# motion_sensor.net
KiCad netlist of a schematic drawn in EAGLE
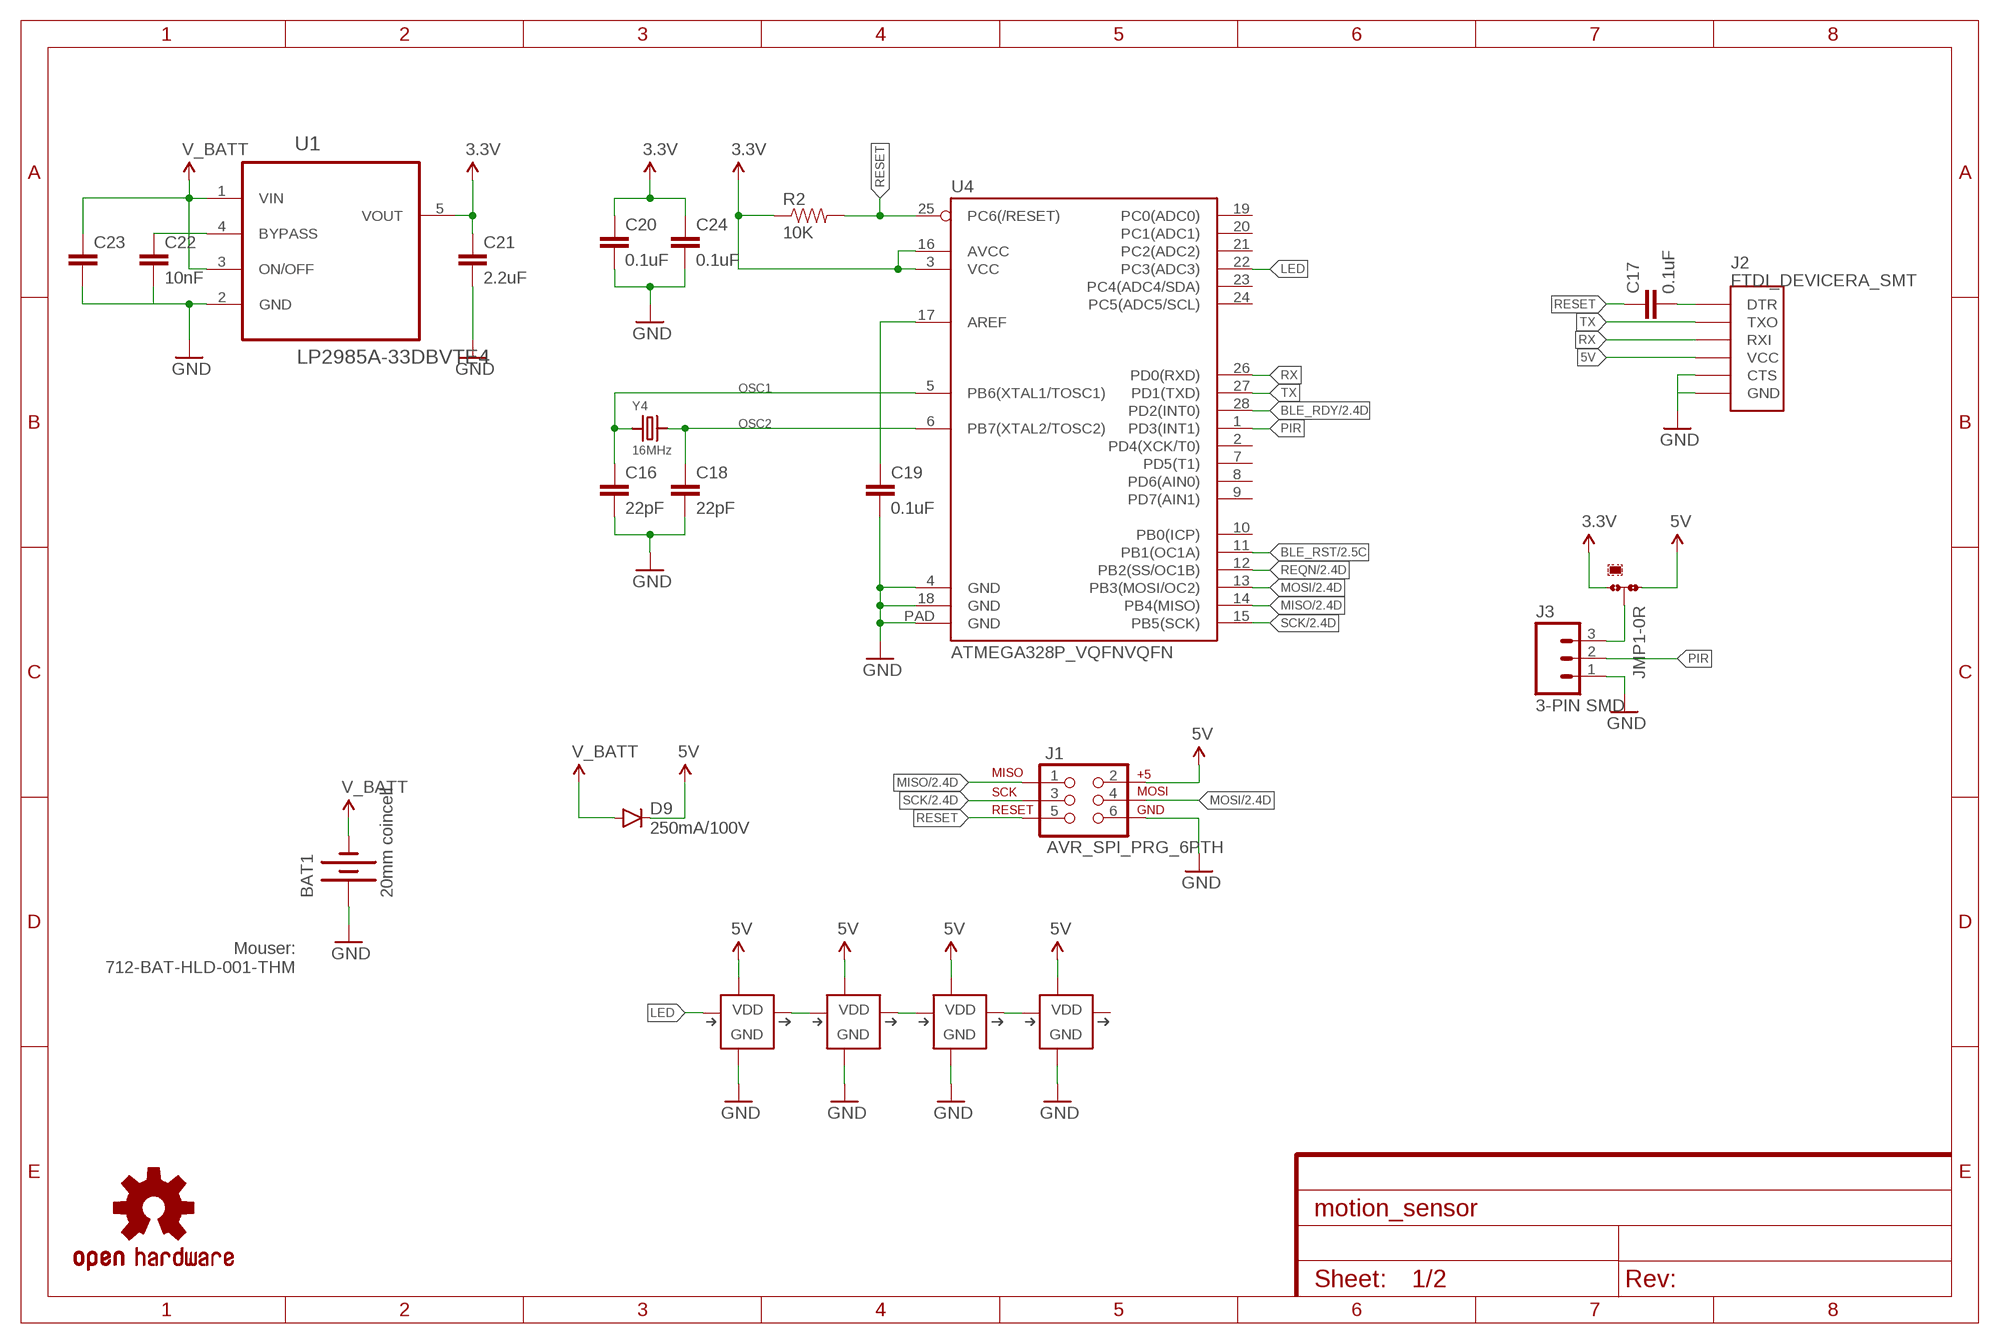
[diagram p0: schematic, sheet 1]
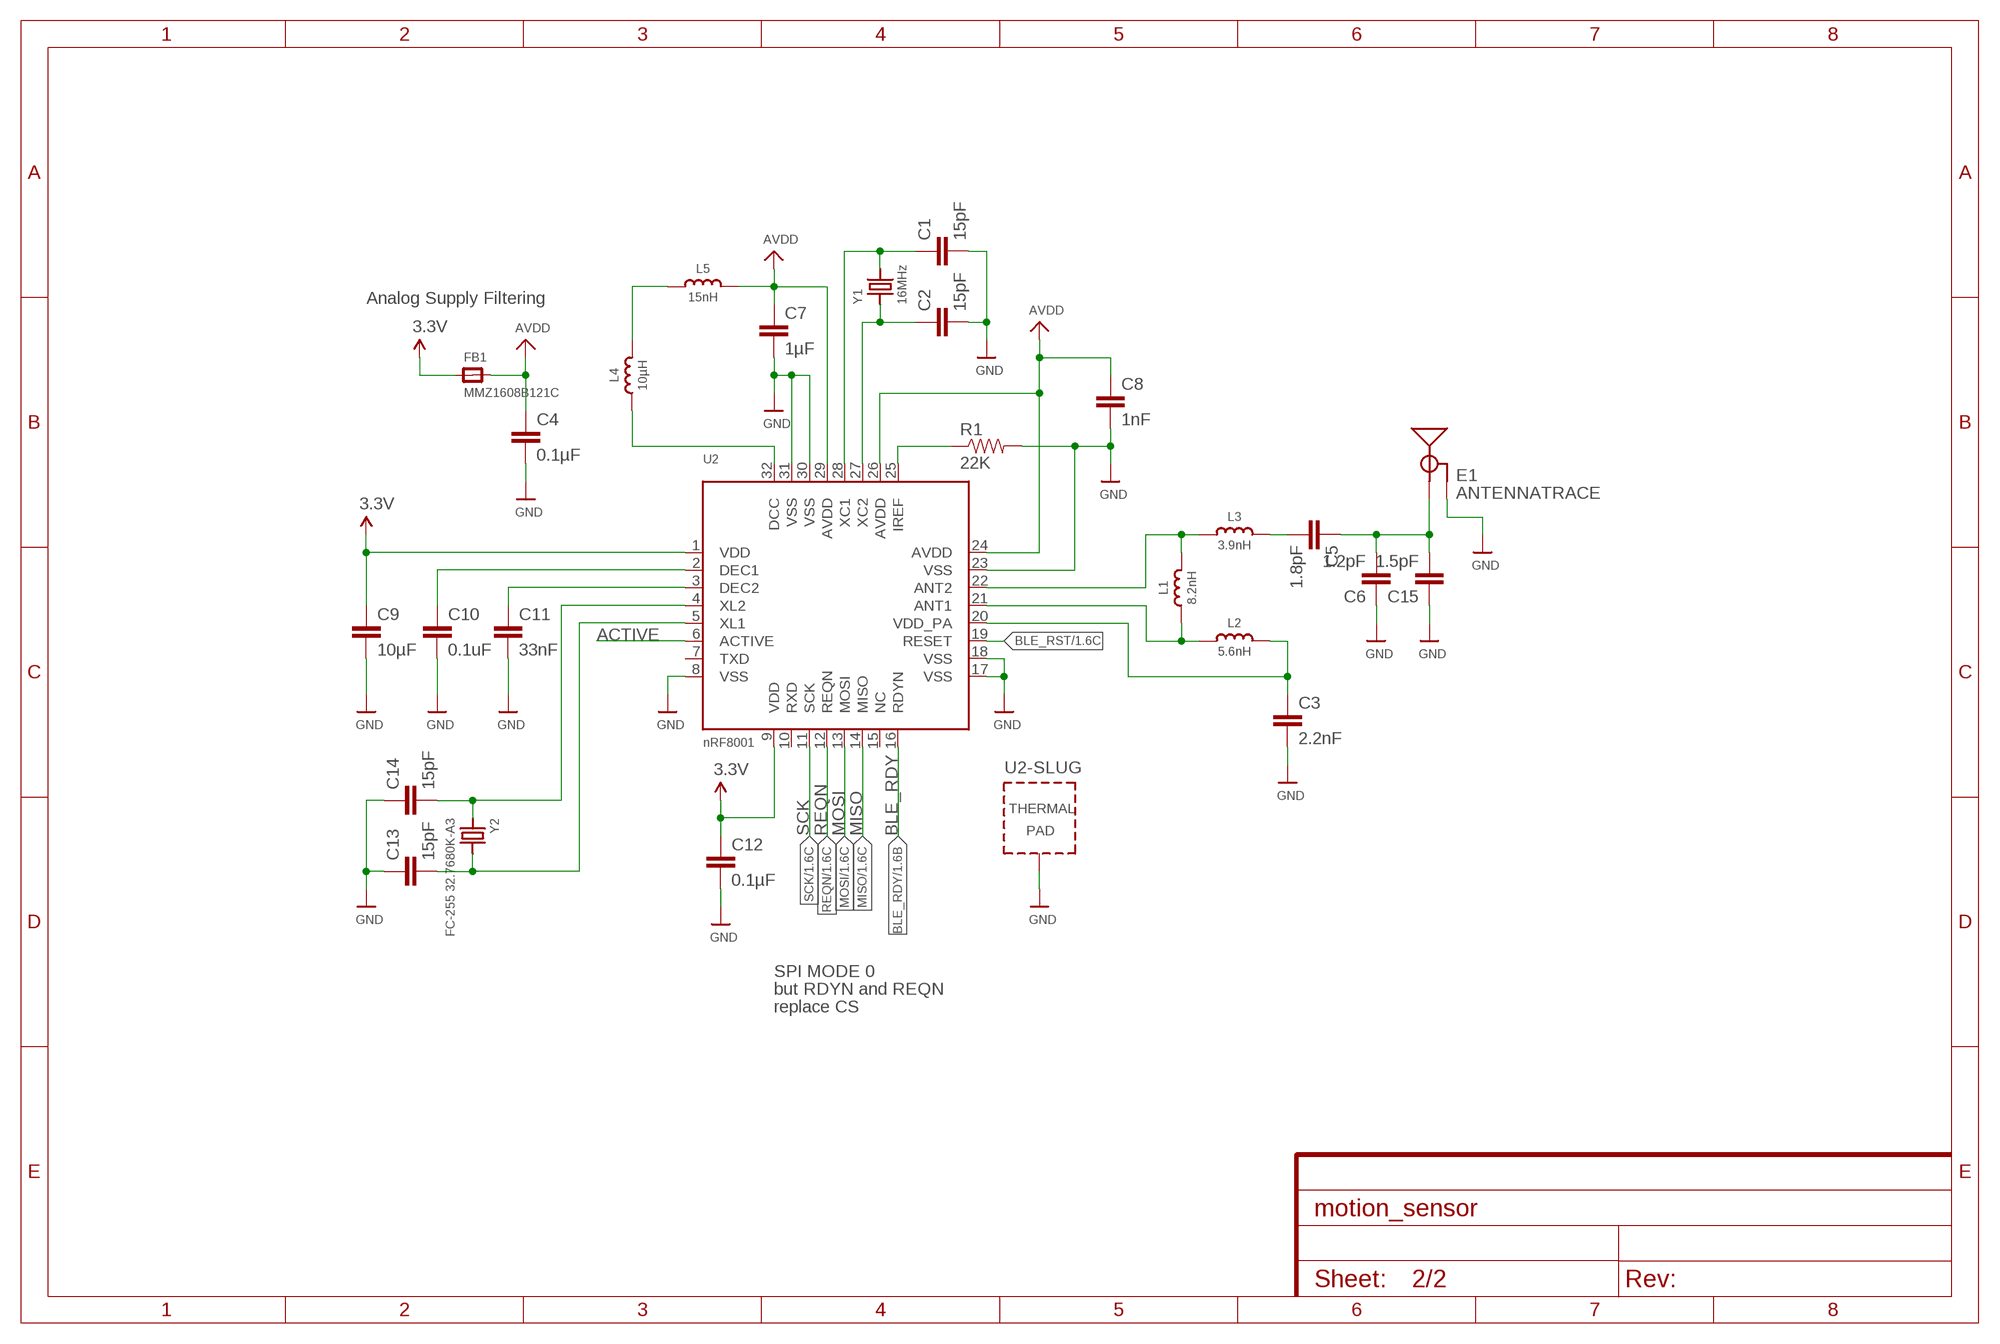
[diagram p1: schematic, sheet 2]

(export (version "E")
  (design (tool "Eeschema 10.0.6"))
  (components
    (comp (ref "BAT1")
      (value "20mm coincell")
      (footprint "eagle-import:BATTCON_20MM_4LEGS")
      (libsource (lib "eagle-import") (part "BATTERY20MM_4LEGS"))
    )
    (comp (ref "C16")
      (value "22pF")
      (footprint "eagle-import:0603-CAP")
      (libsource (lib "eagle-import") (part "22PF-50V-5%(0603)"))
    )
    (comp (ref "C17")
      (value "0.1uF")
      (footprint "eagle-import:0603-CAP")
      (libsource (lib "eagle-import") (part "0.1UF-25V(+80/-20%)(0603)"))
    )
    (comp (ref "C18")
      (value "22pF")
      (footprint "eagle-import:0603-CAP")
      (libsource (lib "eagle-import") (part "22PF-50V-5%(0603)"))
    )
    (comp (ref "C19")
      (value "0.1uF")
      (footprint "eagle-import:0603-CAP")
      (libsource (lib "eagle-import") (part "0.1UF-25V(+80/-20%)(0603)"))
    )
    (comp (ref "C20")
      (value "0.1uF")
      (footprint "eagle-import:0603-CAP")
      (libsource (lib "eagle-import") (part "0.1UF-25V(+80/-20%)(0603)"))
    )
    (comp (ref "C21")
      (value "2.2uF")
      (footprint "eagle-import:0603-CAP")
      (libsource (lib "eagle-import") (part "2.2UF-10V-20%(0603)"))
    )
    (comp (ref "C22")
      (value "10nF")
      (footprint "eagle-import:0603-CAP")
      (libsource (lib "eagle-import") (part "10NF/10000PF-50V-10%(0603)"))
    )
    (comp (ref "C23")
      (value "1UF-25V-10%(0805)\"")
      (footprint "eagle-import:0805-CAP")
      (libsource (lib "eagle-import") (part "1UF-25V-10%(0805){dblquote}"))
    )
    (comp (ref "C24")
      (value "0.1uF")
      (footprint "eagle-import:0603-CAP")
      (libsource (lib "eagle-import") (part "0.1UF-25V(+80/-20%)(0603)"))
    )
    (comp (ref "D9")
      (value "250mA/100V")
      (footprint "eagle-import:SOD-323")
      (libsource (lib "eagle-import") (part "DIODEBAS16"))
    )
    (comp (ref "J1")
      (value "AVR_SPI_PRG_6PTH")
      (footprint "eagle-import:2X3")
      (libsource (lib "eagle-import") (part "AVR_SPI_PRG_6PTH"))
    )
    (comp (ref "J2")
      (value "FTDI_DEVICERA_SMT")
      (footprint "eagle-import:FTDI_DEVICE_RA_SMT")
      (libsource (lib "eagle-import") (part "FTDI_DEVICERA_SMT"))
    )
    (comp (ref "J3")
      (value "3-PIN SMD")
      (footprint "eagle-import:JST-3-SMD")
      (libsource (lib "eagle-import") (part "M03JST-SMD"))
    )
    (comp (ref "JMP1")
      (value "0R-JUMPC")
      (footprint "eagle-import:C0R-JMP")
      (libsource (lib "eagle-import") (part "0R-JUMPC"))
    )
    (comp (ref "LOGO1")
      (value "OSHW-LOGOS")
      (footprint "eagle-import:OSHW-LOGO-S")
      (libsource (lib "eagle-import") (part "OSHW-LOGOS"))
    )
    (comp (ref "R2")
      (value "10K")
      (footprint "eagle-import:0603-RES")
      (libsource (lib "eagle-import") (part "RESISTOR0603-RES"))
    )
    (comp (ref "U$1")
      (value "SK6812MINI")
      (footprint "eagle-import:LED-3535")
      (libsource (lib "eagle-import") (part "SK6812MINI"))
    )
    (comp (ref "U$11")
      (value "SK6812MINI")
      (footprint "eagle-import:LED-3535")
      (libsource (lib "eagle-import") (part "SK6812MINI"))
    )
    (comp (ref "U$15")
      (value "SK6812MINI")
      (footprint "eagle-import:LED-3535")
      (libsource (lib "eagle-import") (part "SK6812MINI"))
    )
    (comp (ref "U$17")
      (value "SK6812MINI")
      (footprint "eagle-import:LED-3535")
      (libsource (lib "eagle-import") (part "SK6812MINI"))
    )
    (comp (ref "U1")
      (value "LP2985A-33DBVTE4")
      (footprint "eagle-import:SOT95P280X145-5N")
      (libsource (lib "eagle-import") (part "LP2985A-33DBVTE4"))
    )
    (comp (ref "U4")
      (value "ATMEGA328P_VQFNVQFN")
      (footprint "eagle-import:VQFN-28")
      (libsource (lib "eagle-import") (part "ATMEGA328P_VQFNVQFN"))
    )
    (comp (ref "Y4")
      (value "16MHz")
      (footprint "eagle-import:CRYSTAL_3.2X2.5")
      (libsource (lib "eagle-import") (part "CRYSTAL3.2X2.5"))
    )
    (comp (ref "C1")
      (value "15pF")
      (footprint "eagle-import:0805")
      (libsource (lib "eagle-import") (part "CAP0805"))
    )
    (comp (ref "C2")
      (value "15pF")
      (footprint "eagle-import:0805")
      (libsource (lib "eagle-import") (part "CAP0805"))
    )
    (comp (ref "C3")
      (value "2.2nF")
      (footprint "eagle-import:0805")
      (libsource (lib "eagle-import") (part "CAP0805"))
    )
    (comp (ref "C4")
      (value "0.1µF")
      (footprint "eagle-import:0805")
      (libsource (lib "eagle-import") (part "CAP0805"))
    )
    (comp (ref "C5")
      (value "1.8pF")
      (footprint "eagle-import:0805")
      (libsource (lib "eagle-import") (part "CAP0805"))
    )
    (comp (ref "C6")
      (value "1.2pF")
      (footprint "eagle-import:0805")
      (libsource (lib "eagle-import") (part "CAP0805"))
    )
    (comp (ref "C7")
      (value "1µF")
      (footprint "eagle-import:0805")
      (libsource (lib "eagle-import") (part "CAP0805"))
    )
    (comp (ref "C8")
      (value "1nF")
      (footprint "eagle-import:0805")
      (libsource (lib "eagle-import") (part "CAP0805"))
    )
    (comp (ref "C9")
      (value "10µF")
      (footprint "eagle-import:0805")
      (libsource (lib "eagle-import") (part "CAP0805"))
    )
    (comp (ref "C10")
      (value "0.1uF")
      (footprint "eagle-import:0805")
      (libsource (lib "eagle-import") (part "CAP0805"))
    )
    (comp (ref "C11")
      (value "33nF")
      (footprint "eagle-import:0805")
      (libsource (lib "eagle-import") (part "CAP0805"))
    )
    (comp (ref "C12")
      (value "0.1µF")
      (footprint "eagle-import:0805")
      (libsource (lib "eagle-import") (part "CAP0805"))
    )
    (comp (ref "C13")
      (value "15pF")
      (footprint "eagle-import:0805")
      (libsource (lib "eagle-import") (part "CAP0805"))
    )
    (comp (ref "C14")
      (value "15pF")
      (footprint "eagle-import:0805")
      (libsource (lib "eagle-import") (part "CAP0805"))
    )
    (comp (ref "C15")
      (value "1.5pF")
      (footprint "eagle-import:0805")
      (libsource (lib "eagle-import") (part "CAP0805"))
    )
    (comp (ref "E1")
      (value "ANTENNATRACE")
      (footprint "eagle-import:TRACE_ANTENNA_2.4GHZ_25.7MM")
      (libsource (lib "eagle-import") (part "ANTENNATRACE"))
    )
    (comp (ref "FB1")
      (value "MMZ1608B121C")
      (footprint "eagle-import:0805")
      (libsource (lib "eagle-import") (part "FERRITE0805"))
    )
    (comp (ref "L1")
      (value "8.2nH")
      (footprint "eagle-import:_0402")
      (libsource (lib "eagle-import") (part "INDUCTOR_0402"))
    )
    (comp (ref "L2")
      (value "5.6nH")
      (footprint "eagle-import:_0402")
      (libsource (lib "eagle-import") (part "INDUCTOR_0402"))
    )
    (comp (ref "L3")
      (value "3.9nH")
      (footprint "eagle-import:_0402")
      (libsource (lib "eagle-import") (part "INDUCTOR_0402"))
    )
    (comp (ref "L4")
      (value "10µH")
      (footprint "eagle-import:_0603")
      (libsource (lib "eagle-import") (part "INDUCTOR_0603"))
    )
    (comp (ref "L5")
      (value "15nH")
      (footprint "eagle-import:_0603")
      (libsource (lib "eagle-import") (part "INDUCTOR_0603"))
    )
    (comp (ref "R1")
      (value "22K")
      (footprint "eagle-import:0603-RES")
      (libsource (lib "eagle-import") (part "RESISTOR0603-RES"))
    )
    (comp (ref "U2")
      (value "nRF8001")
      (footprint "eagle-import:QFN32_5MM")
      (libsource (lib "eagle-import") (part "NRF8001"))
    )
    (comp (ref "Y1")
      (value "16MHz")
      (footprint "eagle-import:CRYSTAL_3.2X2.5")
      (libsource (lib "eagle-import") (part "CRYSTAL3.2X2.5"))
    )
    (comp (ref "Y2")
      (value "FC-255 32.7680K-A3")
      (footprint "eagle-import:CRYSTAL_8X3.8")
      (libsource (lib "eagle-import") (part "CRYSTAL8.0X3.8"))
    )
  )
  (nets
    (net (code "1") (name "3.3V") (class "Default")
      (node (ref "C12") (pin "1") (pinfunction "1_1") (pintype "passive"))
      (node (ref "C20") (pin "1") (pinfunction "1_1") (pintype "passive"))
      (node (ref "C21") (pin "1") (pinfunction "1_1") (pintype "passive"))
      (node (ref "C24") (pin "1") (pinfunction "1_1") (pintype "passive"))
      (node (ref "C9") (pin "1") (pinfunction "1_1") (pintype "passive"))
      (node (ref "FB1") (pin "1") (pinfunction "P$1_1") (pintype "passive"))
      (node (ref "JMP1") (pin "3") (pinfunction "3_3") (pintype "passive"))
      (node (ref "R2") (pin "1") (pinfunction "1_1") (pintype "passive"))
      (node (ref "U1") (pin "5") (pinfunction "VOUT_5") (pintype "output"))
      (node (ref "U2") (pin "1") (pinfunction "VDD_1") (pintype "power_in"))
      (node (ref "U2") (pin "9") (pinfunction "VDD_9") (pintype "power_in"))
      (node (ref "U4") (pin "16") (pinfunction "AVCC_16") (pintype "bidirectional"))
      (node (ref "U4") (pin "3") (pinfunction "VCC_3") (pintype "bidirectional"))
    )
    (net (code "2") (name "5V") (class "Default")
      (node (ref "D9") (pin "C") (pinfunction "C_C") (pintype "passive"))
      (node (ref "J1") (pin "2") (pinfunction "2_2") (pintype "passive"))
      (node (ref "J2") (pin "4") (pinfunction "VCC_4") (pintype "bidirectional"))
      (node (ref "JMP1") (pin "1") (pinfunction "1_1") (pintype "passive"))
      (node (ref "U$1") (pin "3") (pinfunction "VDD_3") (pintype "power_in"))
      (node (ref "U$11") (pin "3") (pinfunction "VDD_3") (pintype "power_in"))
      (node (ref "U$15") (pin "3") (pinfunction "VDD_3") (pintype "power_in"))
      (node (ref "U$17") (pin "3") (pinfunction "VDD_3") (pintype "power_in"))
    )
    (net (code "3") (name "ACTIVE") (class "Default")
      (node (ref "U2") (pin "6") (pinfunction "ACTIVE_6") (pintype "output"))
    )
    (net (code "4") (name "AVDD") (class "Default")
      (node (ref "C4") (pin "1") (pinfunction "1_1") (pintype "passive"))
      (node (ref "C7") (pin "1") (pinfunction "1_1") (pintype "passive"))
      (node (ref "C8") (pin "1") (pinfunction "1_1") (pintype "passive"))
      (node (ref "FB1") (pin "2") (pinfunction "P$2_2") (pintype "passive"))
      (node (ref "L5") (pin "2") (pinfunction "2_2") (pintype "passive"))
      (node (ref "U2") (pin "24") (pinfunction "AVDD_24") (pintype "power_in"))
      (node (ref "U2") (pin "26") (pinfunction "AVDD_26") (pintype "power_in"))
      (node (ref "U2") (pin "29") (pinfunction "AVDD_29") (pintype "power_in"))
    )
    (net (code "5") (name "BLE_RDY") (class "Default")
      (node (ref "U2") (pin "16") (pinfunction "RDYN_16") (pintype "output"))
      (node (ref "U4") (pin "28") (pinfunction "PD2(INT0)_28") (pintype "bidirectional"))
    )
    (net (code "6") (name "BLE_RST") (class "Default")
      (node (ref "U2") (pin "19") (pinfunction "RESET_19") (pintype "input"))
      (node (ref "U4") (pin "11") (pinfunction "PB1(OC1A)_11") (pintype "bidirectional"))
    )
    (net (code "7") (name "GND") (class "Default")
      (node (ref "BAT1") (pin "POSITIVE@1") (pinfunction "+_POSITIVE@1") (pintype "power_in"))
      (node (ref "BAT1") (pin "POSITIVE@2") (pinfunction "+_POSITIVE@2") (pintype "power_in"))
      (node (ref "BAT1") (pin "POSITIVE@3") (pinfunction "+_POSITIVE@3") (pintype "power_in"))
      (node (ref "BAT1") (pin "POSITIVE@4") (pinfunction "+_POSITIVE@4") (pintype "power_in"))
      (node (ref "C1") (pin "2") (pinfunction "2_2") (pintype "passive"))
      (node (ref "C10") (pin "2") (pinfunction "2_2") (pintype "passive"))
      (node (ref "C11") (pin "2") (pinfunction "2_2") (pintype "passive"))
      (node (ref "C12") (pin "2") (pinfunction "2_2") (pintype "passive"))
      (node (ref "C13") (pin "1") (pinfunction "1_1") (pintype "passive"))
      (node (ref "C14") (pin "1") (pinfunction "1_1") (pintype "passive"))
      (node (ref "C15") (pin "1") (pinfunction "1_1") (pintype "passive"))
      (node (ref "C16") (pin "2") (pinfunction "2_2") (pintype "passive"))
      (node (ref "C18") (pin "2") (pinfunction "2_2") (pintype "passive"))
      (node (ref "C19") (pin "2") (pinfunction "2_2") (pintype "passive"))
      (node (ref "C2") (pin "2") (pinfunction "2_2") (pintype "passive"))
      (node (ref "C20") (pin "2") (pinfunction "2_2") (pintype "passive"))
      (node (ref "C21") (pin "2") (pinfunction "2_2") (pintype "passive"))
      (node (ref "C22") (pin "2") (pinfunction "2_2") (pintype "passive"))
      (node (ref "C23") (pin "2") (pinfunction "2_2") (pintype "passive"))
      (node (ref "C24") (pin "2") (pinfunction "2_2") (pintype "passive"))
      (node (ref "C3") (pin "2") (pinfunction "2_2") (pintype "passive"))
      (node (ref "C4") (pin "2") (pinfunction "2_2") (pintype "passive"))
      (node (ref "C6") (pin "1") (pinfunction "1_1") (pintype "passive"))
      (node (ref "C7") (pin "2") (pinfunction "2_2") (pintype "passive"))
      (node (ref "C8") (pin "2") (pinfunction "2_2") (pintype "passive"))
      (node (ref "C9") (pin "2") (pinfunction "2_2") (pintype "passive"))
      (node (ref "E1") (pin "GND") (pinfunction "GND_GND") (pintype "bidirectional"))
      (node (ref "E1") (pin "GND2") (pinfunction "GND_GND2") (pintype "bidirectional"))
      (node (ref "J1") (pin "6") (pinfunction "6_6") (pintype "passive"))
      (node (ref "J2") (pin "5") (pinfunction "CTS_5") (pintype "bidirectional"))
      (node (ref "J2") (pin "6") (pinfunction "GND_6") (pintype "bidirectional"))
      (node (ref "J3") (pin "1") (pinfunction "1_1") (pintype "passive"))
      (node (ref "R1") (pin "2") (pinfunction "2_2") (pintype "passive"))
      (node (ref "U$1") (pin "1") (pinfunction "GND_1") (pintype "power_in"))
      (node (ref "U$11") (pin "1") (pinfunction "GND_1") (pintype "power_in"))
      (node (ref "U$15") (pin "1") (pinfunction "GND_1") (pintype "power_in"))
      (node (ref "U$17") (pin "1") (pinfunction "GND_1") (pintype "power_in"))
      (node (ref "U1") (pin "2") (pinfunction "GND_2") (pintype "passive"))
      (node (ref "U2") (pin "17") (pinfunction "VSS_17") (pintype "power_in"))
      (node (ref "U2") (pin "18") (pinfunction "VSS_18") (pintype "power_in"))
      (node (ref "U2") (pin "23") (pinfunction "VSS_23") (pintype "power_in"))
      (node (ref "U2") (pin "30") (pinfunction "VSS_30") (pintype "power_in"))
      (node (ref "U2") (pin "31") (pinfunction "VSS_31") (pintype "power_in"))
      (node (ref "U2") (pin "33") (pinfunction "TP_33") (pintype "power_in"))
      (node (ref "U2") (pin "8") (pinfunction "VSS_8") (pintype "power_in"))
      (node (ref "U4") (pin "18") (pinfunction "GND_18") (pintype "bidirectional"))
      (node (ref "U4") (pin "4") (pinfunction "GND_4") (pintype "bidirectional"))
      (node (ref "U4") (pin "PAD") (pinfunction "GND_PAD") (pintype "bidirectional"))
    )
    (net (code "8") (name "LED") (class "Default")
      (node (ref "U$1") (pin "2") (pinfunction "DI_2") (pintype "input"))
      (node (ref "U4") (pin "22") (pinfunction "PC3(ADC3)_22") (pintype "bidirectional"))
    )
    (net (code "9") (name "MISO") (class "Default")
      (node (ref "J1") (pin "1") (pinfunction "1_1") (pintype "passive"))
      (node (ref "U2") (pin "14") (pinfunction "MISO_14") (pintype "output"))
      (node (ref "U4") (pin "14") (pinfunction "PB4(MISO)_14") (pintype "bidirectional"))
    )
    (net (code "10") (name "MOSI") (class "Default")
      (node (ref "J1") (pin "4") (pinfunction "4_4") (pintype "passive"))
      (node (ref "U2") (pin "13") (pinfunction "MOSI_13") (pintype "input"))
      (node (ref "U4") (pin "13") (pinfunction "PB3(MOSI/OC2)_13") (pintype "bidirectional"))
    )
    (net (code "11") (name "Net-(C5-Pad2)") (class "Default")
      (node (ref "C5") (pin "2") (pinfunction "2_2") (pintype "passive"))
      (node (ref "L3") (pin "2") (pinfunction "2_2") (pintype "passive"))
    )
    (net (code "12") (name "Net-(E1-SIGNAL)") (class "Default")
      (node (ref "C15") (pin "2") (pinfunction "2_2") (pintype "passive"))
      (node (ref "C5") (pin "1") (pinfunction "1_1") (pintype "passive"))
      (node (ref "C6") (pin "2") (pinfunction "2_2") (pintype "passive"))
      (node (ref "E1") (pin "ANT") (pinfunction "SIGNAL_ANT") (pintype "bidirectional"))
    )
    (net (code "13") (name "Net-(J2-DTR)") (class "Default")
      (node (ref "C17") (pin "2") (pinfunction "2_2") (pintype "passive"))
      (node (ref "J2") (pin "1") (pinfunction "DTR_1") (pintype "bidirectional"))
    )
    (net (code "14") (name "Net-(J3-Pad3)") (class "Default")
      (node (ref "J3") (pin "3") (pinfunction "3_3") (pintype "passive"))
      (node (ref "JMP1") (pin "2") (pinfunction "2_2") (pintype "passive"))
    )
    (net (code "15") (name "Net-(L4-Pad2)") (class "Default")
      (node (ref "L4") (pin "2") (pinfunction "2_2") (pintype "passive"))
      (node (ref "L5") (pin "1") (pinfunction "1_1") (pintype "passive"))
    )
    (net (code "16") (name "Net-(U$1-DO)") (class "Default")
      (node (ref "U$1") (pin "4") (pinfunction "DO_4") (pintype "output"))
      (node (ref "U$11") (pin "2") (pinfunction "DI_2") (pintype "input"))
    )
    (net (code "17") (name "Net-(U$11-DO)") (class "Default")
      (node (ref "U$11") (pin "4") (pinfunction "DO_4") (pintype "output"))
      (node (ref "U$15") (pin "2") (pinfunction "DI_2") (pintype "input"))
    )
    (net (code "18") (name "Net-(U$15-DO)") (class "Default")
      (node (ref "U$15") (pin "4") (pinfunction "DO_4") (pintype "output"))
      (node (ref "U$17") (pin "2") (pinfunction "DI_2") (pintype "input"))
    )
    (net (code "19") (name "Net-(U1-BYPASS)") (class "Default")
      (node (ref "C22") (pin "1") (pinfunction "1_1") (pintype "passive"))
      (node (ref "U1") (pin "4") (pinfunction "BYPASS_4") (pintype "input"))
    )
    (net (code "20") (name "Net-(U2B-ANT1)") (class "Default")
      (node (ref "L1") (pin "1") (pinfunction "1_1") (pintype "passive"))
      (node (ref "L2") (pin "1") (pinfunction "1_1") (pintype "passive"))
      (node (ref "U2") (pin "21") (pinfunction "ANT1_21") (pintype "bidirectional"))
    )
    (net (code "21") (name "Net-(U2B-ANT2)") (class "Default")
      (node (ref "L1") (pin "2") (pinfunction "2_2") (pintype "passive"))
      (node (ref "L3") (pin "1") (pinfunction "1_1") (pintype "passive"))
      (node (ref "U2") (pin "22") (pinfunction "ANT2_22") (pintype "bidirectional"))
    )
    (net (code "22") (name "Net-(U2B-DCC)") (class "Default")
      (node (ref "L4") (pin "1") (pinfunction "1_1") (pintype "passive"))
      (node (ref "U2") (pin "32") (pinfunction "DCC_32") (pintype "bidirectional"))
    )
    (net (code "23") (name "Net-(U2B-DEC1)") (class "Default")
      (node (ref "C10") (pin "1") (pinfunction "1_1") (pintype "passive"))
      (node (ref "U2") (pin "2") (pinfunction "DEC1_2") (pintype "bidirectional"))
    )
    (net (code "24") (name "Net-(U2B-DEC2)") (class "Default")
      (node (ref "C11") (pin "1") (pinfunction "1_1") (pintype "passive"))
      (node (ref "U2") (pin "3") (pinfunction "DEC2_3") (pintype "bidirectional"))
    )
    (net (code "25") (name "Net-(U2B-IREF)") (class "Default")
      (node (ref "R1") (pin "1") (pinfunction "1_1") (pintype "passive"))
      (node (ref "U2") (pin "25") (pinfunction "IREF_25") (pintype "output"))
    )
    (net (code "26") (name "Net-(U2B-VDD_PA)") (class "Default")
      (node (ref "C3") (pin "1") (pinfunction "1_1") (pintype "passive"))
      (node (ref "L2") (pin "2") (pinfunction "2_2") (pintype "passive"))
      (node (ref "U2") (pin "20") (pinfunction "VDD_PA_20") (pintype "bidirectional"))
    )
    (net (code "27") (name "Net-(U2B-XC1)") (class "Default")
      (node (ref "C1") (pin "1") (pinfunction "1_1") (pintype "passive"))
      (node (ref "U2") (pin "28") (pinfunction "XC1_28") (pintype "input"))
      (node (ref "Y1") (pin "2") (pinfunction "2_2") (pintype "passive"))
    )
    (net (code "28") (name "Net-(U2B-XC2)") (class "Default")
      (node (ref "C2") (pin "1") (pinfunction "1_1") (pintype "passive"))
      (node (ref "U2") (pin "27") (pinfunction "XC2_27") (pintype "output"))
      (node (ref "Y1") (pin "1") (pinfunction "1_1") (pintype "passive"))
    )
    (net (code "29") (name "Net-(U2B-XL1)") (class "Default")
      (node (ref "C13") (pin "2") (pinfunction "2_2") (pintype "passive"))
      (node (ref "U2") (pin "5") (pinfunction "XL1_5") (pintype "input"))
      (node (ref "Y2") (pin "P$4") (pinfunction "2_P$4") (pintype "passive"))
    )
    (net (code "30") (name "Net-(U2B-XL2)") (class "Default")
      (node (ref "C14") (pin "2") (pinfunction "2_2") (pintype "passive"))
      (node (ref "U2") (pin "4") (pinfunction "XL2_4") (pintype "output"))
      (node (ref "Y2") (pin "P$1") (pinfunction "1_P$1") (pintype "passive"))
    )
    (net (code "31") (name "Net-(U4-AREF)") (class "Default")
      (node (ref "C19") (pin "1") (pinfunction "1_1") (pintype "passive"))
      (node (ref "U4") (pin "17") (pinfunction "AREF_17") (pintype "bidirectional"))
    )
    (net (code "32") (name "OSC1") (class "Default")
      (node (ref "C16") (pin "1") (pinfunction "1_1") (pintype "passive"))
      (node (ref "U4") (pin "5") (pinfunction "PB6(XTAL1/TOSC1)_5") (pintype "bidirectional"))
      (node (ref "Y4") (pin "1") (pinfunction "1_1") (pintype "passive"))
    )
    (net (code "33") (name "OSC2") (class "Default")
      (node (ref "C18") (pin "1") (pinfunction "1_1") (pintype "passive"))
      (node (ref "U4") (pin "6") (pinfunction "PB7(XTAL2/TOSC2)_6") (pintype "bidirectional"))
      (node (ref "Y4") (pin "2") (pinfunction "2_2") (pintype "passive"))
    )
    (net (code "34") (name "PIR") (class "Default")
      (node (ref "J3") (pin "2") (pinfunction "2_2") (pintype "passive"))
      (node (ref "U4") (pin "1") (pinfunction "PD3(INT1)_1") (pintype "bidirectional"))
    )
    (net (code "35") (name "REQN") (class "Default")
      (node (ref "U2") (pin "12") (pinfunction "REQN_12") (pintype "input"))
      (node (ref "U4") (pin "12") (pinfunction "PB2(SS/OC1B)_12") (pintype "bidirectional"))
    )
    (net (code "36") (name "RESET") (class "Default")
      (node (ref "C17") (pin "1") (pinfunction "1_1") (pintype "passive"))
      (node (ref "J1") (pin "5") (pinfunction "5_5") (pintype "passive"))
      (node (ref "R2") (pin "2") (pinfunction "2_2") (pintype "passive"))
      (node (ref "U4") (pin "25") (pinfunction "PC6(/RESET)_25") (pintype "bidirectional"))
    )
    (net (code "37") (name "RX") (class "Default")
      (node (ref "J2") (pin "3") (pinfunction "RXI_3") (pintype "bidirectional"))
      (node (ref "U4") (pin "26") (pinfunction "PD0(RXD)_26") (pintype "bidirectional"))
    )
    (net (code "38") (name "SCK") (class "Default")
      (node (ref "J1") (pin "3") (pinfunction "3_3") (pintype "passive"))
      (node (ref "U2") (pin "11") (pinfunction "SCK_11") (pintype "input"))
      (node (ref "U4") (pin "15") (pinfunction "PB5(SCK)_15") (pintype "bidirectional"))
    )
    (net (code "39") (name "TX") (class "Default")
      (node (ref "J2") (pin "2") (pinfunction "TXO_2") (pintype "bidirectional"))
      (node (ref "U4") (pin "27") (pinfunction "PD1(TXD)_27") (pintype "bidirectional"))
    )
    (net (code "40") (name "V_BATT") (class "Default")
      (node (ref "BAT1") (pin "NEGATIVE") (pinfunction "-_NEGATIVE") (pintype "power_in"))
      (node (ref "C23") (pin "1") (pinfunction "1_1") (pintype "passive"))
      (node (ref "D9") (pin "A") (pinfunction "A_A") (pintype "passive"))
      (node (ref "U1") (pin "1") (pinfunction "VIN_1") (pintype "power_in"))
      (node (ref "U1") (pin "3") (pinfunction "ON/OFF_3") (pintype "input"))
    )
    (net (code "41") (name "unconnected-(U$17-DO-Pad4)") (class "Default")
      (node (ref "U$17") (pin "4") (pinfunction "DO_4") (pintype "output"))
    )
    (net (code "42") (name "unconnected-(U2B-NC-Pad15)") (class "Default")
      (node (ref "U2") (pin "15") (pinfunction "NC_15") (pintype "no_connect"))
    )
    (net (code "43") (name "unconnected-(U2B-RXD-Pad10)") (class "Default")
      (node (ref "U2") (pin "10") (pinfunction "RXD_10") (pintype "input"))
    )
    (net (code "44") (name "unconnected-(U2B-TXD-Pad7)") (class "Default")
      (node (ref "U2") (pin "7") (pinfunction "TXD_7") (pintype "output"))
    )
    (net (code "45") (name "unconnected-(U4-PB0(ICP)-Pad10)") (class "Default")
      (node (ref "U4") (pin "10") (pinfunction "PB0(ICP)_10") (pintype "bidirectional"))
    )
    (net (code "46") (name "unconnected-(U4-PC0(ADC0)-Pad19)") (class "Default")
      (node (ref "U4") (pin "19") (pinfunction "PC0(ADC0)_19") (pintype "bidirectional"))
    )
    (net (code "47") (name "unconnected-(U4-PC1(ADC1)-Pad20)") (class "Default")
      (node (ref "U4") (pin "20") (pinfunction "PC1(ADC1)_20") (pintype "bidirectional"))
    )
    (net (code "48") (name "unconnected-(U4-PC2(ADC2)-Pad21)") (class "Default")
      (node (ref "U4") (pin "21") (pinfunction "PC2(ADC2)_21") (pintype "bidirectional"))
    )
    (net (code "49") (name "unconnected-(U4-PC4(ADC4{slash}SDA)-Pad23)") (class "Default")
      (node (ref "U4") (pin "23") (pinfunction "PC4(ADC4/SDA)_23") (pintype "bidirectional"))
    )
    (net (code "50") (name "unconnected-(U4-PC5(ADC5{slash}SCL)-Pad24)") (class "Default")
      (node (ref "U4") (pin "24") (pinfunction "PC5(ADC5/SCL)_24") (pintype "bidirectional"))
    )
    (net (code "51") (name "unconnected-(U4-PD4(XCK{slash}T0)-Pad2)") (class "Default")
      (node (ref "U4") (pin "2") (pinfunction "PD4(XCK/T0)_2") (pintype "bidirectional"))
    )
    (net (code "52") (name "unconnected-(U4-PD5(T1)-Pad7)") (class "Default")
      (node (ref "U4") (pin "7") (pinfunction "PD5(T1)_7") (pintype "bidirectional"))
    )
    (net (code "53") (name "unconnected-(U4-PD6(AIN0)-Pad8)") (class "Default")
      (node (ref "U4") (pin "8") (pinfunction "PD6(AIN0)_8") (pintype "bidirectional"))
    )
    (net (code "54") (name "unconnected-(U4-PD7(AIN1)-Pad9)") (class "Default")
      (node (ref "U4") (pin "9") (pinfunction "PD7(AIN1)_9") (pintype "bidirectional"))
    )
  )
)
